# Control.net
KiCad netlist of a schematic drawn in Altium Designer
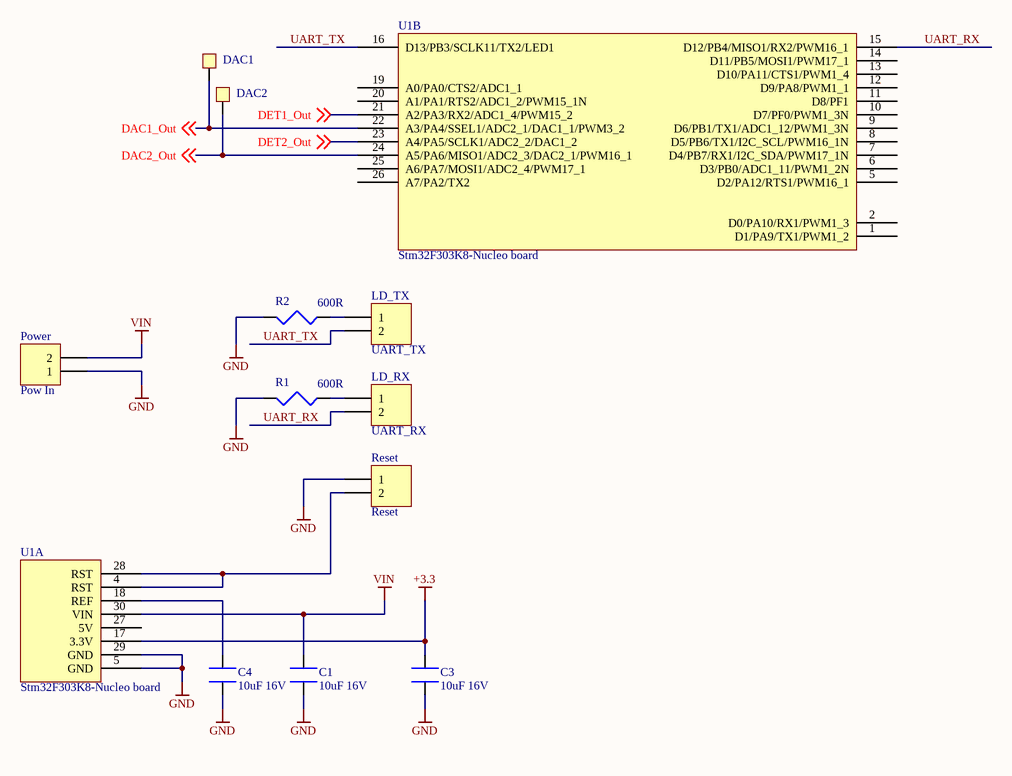
[diagram p0: Control.SchDoc]

(export (version "E")
  (design (tool "Eeschema 10.0.6"))
  (components
    (comp (ref "C1") (value "10uF 16V") (footprint "0805_C") (libsource (lib "Schlib1") (part "Cap")))
    (comp (ref "C3") (value "10uF 16V") (footprint "0805_C") (libsource (lib "Schlib1") (part "Cap")))
    (comp (ref "C4") (value "10uF 16V") (footprint "0805_C") (libsource (lib "Schlib1") (part "Cap")))
    (comp (ref "DAC1") (value "Point") (footprint "Test_Point") (libsource (lib "Schlib1") (part "Point")))
    (comp (ref "DAC2") (value "Point") (footprint "Test_Point") (libsource (lib "Schlib1") (part "Point")))
    (comp (ref "LD_RX")
      (value "UART_RX")
      (footprint "HDR1X2")
      (description "Header, 2-Pin")
      (fields (field (name "PUBLISHER") "Altium Limited"))
      (libsource (lib "Miscellaneous Connectors") (part "Header 2"))
    )
    (comp (ref "LD_TX")
      (value "UART_TX")
      (footprint "HDR1X2")
      (description "Header, 2-Pin")
      (fields (field (name "PUBLISHER") "Altium Limited"))
      (libsource (lib "Miscellaneous Connectors") (part "Header 2"))
    )
    (comp (ref "Power")
      (value "Pow In")
      (footprint "HDR1X2")
      (description "Header, 2-Pin")
      (fields (field (name "PUBLISHER") "Altium Limited"))
      (libsource (lib "") (part "Header 2_1"))
    )
    (comp (ref "R1") (value "600R") (footprint "0805_R") (libsource (lib "Schlib1") (part "Res")))
    (comp (ref "R2") (value "600R") (footprint "0805_R") (libsource (lib "Schlib1") (part "Res")))
    (comp (ref "Reset")
      (value "Reset")
      (footprint "HDR1X2")
      (description "Header, 2-Pin")
      (fields (field (name "PUBLISHER") "Altium Limited"))
      (libsource (lib "Miscellaneous Connectors") (part "Header 2"))
    )
    (comp (ref "U1")
      (value "Stm32F303K8-Nucleo board")
      (footprint "F303-Nucleo")
      (libsource (lib "Schlib1") (part "F303-Nucleo"))
    )
  )
  (nets
    (net (code "1") (name "+3.3") (class "Default")
      (node (ref "C3") (pin "1") (pinfunction "1_1") (pintype "passive"))
      (node (ref "U1") (pin "17") (pinfunction "3.3V_17") (pintype "passive"))
    )
    (net (code "2") (name "/UART_RX") (class "Default")
      (node (ref "LD_RX") (pin "2") (pinfunction "2_2") (pintype "passive"))
      (node (ref "U1") (pin "15") (pinfunction "D12/PB4/MISO1/RX2/PWM16_1_15") (pintype "passive"))
    )
    (net (code "3") (name "/UART_TX") (class "Default")
      (node (ref "LD_TX") (pin "2") (pinfunction "2_2") (pintype "passive"))
      (node (ref "U1") (pin "16") (pinfunction "D13/PB3/SCLK11/TX2/LED1_16") (pintype "passive"))
    )
    (net (code "4") (name "DAC1_Out") (class "Default")
      (node (ref "DAC1") (pin "1") (pinfunction "1_1") (pintype "passive"))
      (node (ref "U1") (pin "22") (pinfunction "A3/PA4/SSEL1/ADC2_1/DAC1_1/PWM3_2_22") (pintype "passive"))
    )
    (net (code "5") (name "DAC2_Out") (class "Default")
      (node (ref "DAC2") (pin "1") (pinfunction "1_1") (pintype "passive"))
      (node (ref "U1") (pin "24") (pinfunction "A5/PA6/MISO1/ADC2_3/DAC2_1/PWM16_1_24") (pintype "passive"))
    )
    (net (code "6") (name "DET1_Out") (class "Default")
      (node (ref "U1") (pin "21") (pinfunction "A2/PA3/RX2/ADC1_4/PWM15_2_21") (pintype "passive"))
    )
    (net (code "7") (name "DET2_Out") (class "Default")
      (node (ref "U1") (pin "23") (pinfunction "A4/PA5/SCLK1/ADC2_2/DAC1_2_23") (pintype "passive"))
    )
    (net (code "8") (name "GND") (class "Default")
      (node (ref "C1") (pin "2") (pinfunction "2_2") (pintype "passive"))
      (node (ref "C3") (pin "2") (pinfunction "2_2") (pintype "passive"))
      (node (ref "C4") (pin "2") (pinfunction "2_2") (pintype "passive"))
      (node (ref "Power") (pin "1") (pinfunction "1_1") (pintype "passive"))
      (node (ref "R1") (pin "1") (pinfunction "1_1") (pintype "passive"))
      (node (ref "R2") (pin "1") (pinfunction "1_1") (pintype "passive"))
      (node (ref "Reset") (pin "1") (pinfunction "1_1") (pintype "passive"))
      (node (ref "U1") (pin "29") (pinfunction "GND_29") (pintype "passive"))
      (node (ref "U1") (pin "5") (pinfunction "GND_5") (pintype "passive"))
    )
    (net (code "9") (name "Net-(LD_RX-Pad1)") (class "Default")
      (node (ref "LD_RX") (pin "1") (pinfunction "1_1") (pintype "passive"))
      (node (ref "R1") (pin "2") (pinfunction "2_2") (pintype "passive"))
    )
    (net (code "10") (name "Net-(LD_TX-Pad1)") (class "Default")
      (node (ref "LD_TX") (pin "1") (pinfunction "1_1") (pintype "passive"))
      (node (ref "R2") (pin "2") (pinfunction "2_2") (pintype "passive"))
    )
    (net (code "11") (name "Net-(Reset-Pad2)") (class "Default")
      (node (ref "Reset") (pin "2") (pinfunction "2_2") (pintype "passive"))
      (node (ref "U1") (pin "28") (pinfunction "RST_28") (pintype "passive"))
      (node (ref "U1") (pin "4") (pinfunction "RST_4") (pintype "passive"))
    )
    (net (code "12") (name "Net-(U1A-REF)") (class "Default")
      (node (ref "C4") (pin "1") (pinfunction "1_1") (pintype "passive"))
      (node (ref "U1") (pin "18") (pinfunction "REF_18") (pintype "passive"))
    )
    (net (code "13") (name "VIN") (class "Default")
      (node (ref "C1") (pin "1") (pinfunction "1_1") (pintype "passive"))
      (node (ref "Power") (pin "2") (pinfunction "2_2") (pintype "passive"))
      (node (ref "U1") (pin "30") (pinfunction "VIN_30") (pintype "passive"))
    )
    (net (code "14") (name "unconnected-(U1A-5V-Pad27)") (class "Default")
      (node (ref "U1") (pin "27") (pinfunction "5V_27") (pintype "passive"))
    )
    (net (code "15") (name "unconnected-(U1B-A0{slash}PA0{slash}CTS2{slash}ADC1_1-Pad19)") (class "Default")
      (node (ref "U1") (pin "19") (pinfunction "A0/PA0/CTS2/ADC1_1_19") (pintype "passive"))
    )
    (net (code "16") (name "unconnected-(U1B-A1{slash}PA1{slash}RTS2{slash}ADC1_2{slash}PWM15_1N-Pad20)") (class "Default")
      (node (ref "U1") (pin "20") (pinfunction "A1/PA1/RTS2/ADC1_2/PWM15_1N_20") (pintype "passive"))
    )
    (net (code "17") (name "unconnected-(U1B-A6{slash}PA7{slash}MOSI1{slash}ADC2_4{slash}PWM17_1-Pad25)") (class "Default")
      (node (ref "U1") (pin "25") (pinfunction "A6/PA7/MOSI1/ADC2_4/PWM17_1_25") (pintype "passive"))
    )
    (net (code "18") (name "unconnected-(U1B-A7{slash}PA2{slash}TX2-Pad26)") (class "Default")
      (node (ref "U1") (pin "26") (pinfunction "A7/PA2/TX2_26") (pintype "passive"))
    )
    (net (code "19") (name "unconnected-(U1B-D0{slash}PA10{slash}RX1{slash}PWM1_3-Pad2)") (class "Default")
      (node (ref "U1") (pin "2") (pinfunction "D0/PA10/RX1/PWM1_3_2") (pintype "passive"))
    )
    (net (code "20") (name "unconnected-(U1B-D1{slash}PA9{slash}TX1{slash}PWM1_2-Pad1)") (class "Default")
      (node (ref "U1") (pin "1") (pinfunction "D1/PA9/TX1/PWM1_2_1") (pintype "passive"))
    )
    (net (code "21") (name "unconnected-(U1B-D2{slash}PA12{slash}RTS1{slash}PWM16_1-Pad5)") (class "Default")
      (node (ref "U1") (pin "5") (pinfunction "D2/PA12/RTS1/PWM16_1_5") (pintype "passive"))
    )
    (net (code "22") (name "unconnected-(U1B-D3{slash}PB0{slash}ADC1_11{slash}PWM1_2N-Pad6)") (class "Default")
      (node (ref "U1") (pin "6") (pinfunction "D3/PB0/ADC1_11/PWM1_2N_6") (pintype "passive"))
    )
    (net (code "23") (name "unconnected-(U1B-D4{slash}PB7{slash}RX1{slash}I2C_SDA{slash}PWM17_1N-Pad7)") (class "Default")
      (node (ref "U1") (pin "7") (pinfunction "D4/PB7/RX1/I2C_SDA/PWM17_1N_7") (pintype "passive"))
    )
    (net (code "24") (name "unconnected-(U1B-D5{slash}PB6{slash}TX1{slash}I2C_SCL{slash}PWM16_1N-Pad8)") (class "Default")
      (node (ref "U1") (pin "8") (pinfunction "D5/PB6/TX1/I2C_SCL/PWM16_1N_8") (pintype "passive"))
    )
    (net (code "25") (name "unconnected-(U1B-D6{slash}PB1{slash}TX1{slash}ADC1_12{slash}PWM1_3N-Pad9)") (class "Default")
      (node (ref "U1") (pin "9") (pinfunction "D6/PB1/TX1/ADC1_12/PWM1_3N_9") (pintype "passive"))
    )
    (net (code "26") (name "unconnected-(U1B-D7{slash}PF0{slash}PWM1_3N-Pad10)") (class "Default")
      (node (ref "U1") (pin "10") (pinfunction "D7/PF0/PWM1_3N_10") (pintype "passive"))
    )
    (net (code "27") (name "unconnected-(U1B-D8{slash}PF1-Pad11)") (class "Default")
      (node (ref "U1") (pin "11") (pinfunction "D8/PF1_11") (pintype "passive"))
    )
    (net (code "28") (name "unconnected-(U1B-D9{slash}PA8{slash}PWM1_1-Pad12)") (class "Default")
      (node (ref "U1") (pin "12") (pinfunction "D9/PA8/PWM1_1_12") (pintype "passive"))
    )
    (net (code "29") (name "unconnected-(U1B-D10{slash}PA11{slash}CTS1{slash}PWM1_4-Pad13)") (class "Default")
      (node (ref "U1") (pin "13") (pinfunction "D10/PA11/CTS1/PWM1_4_13") (pintype "passive"))
    )
    (net (code "30") (name "unconnected-(U1B-D11{slash}PB5{slash}MOSI1{slash}PWM17_1-Pad14)") (class "Default")
      (node (ref "U1") (pin "14") (pinfunction "D11/PB5/MOSI1/PWM17_1_14") (pintype "passive"))
    )
  )
)
